# QCopterRC_LCD_Sch.net
KiCad netlist of a schematic drawn in Altium Designer
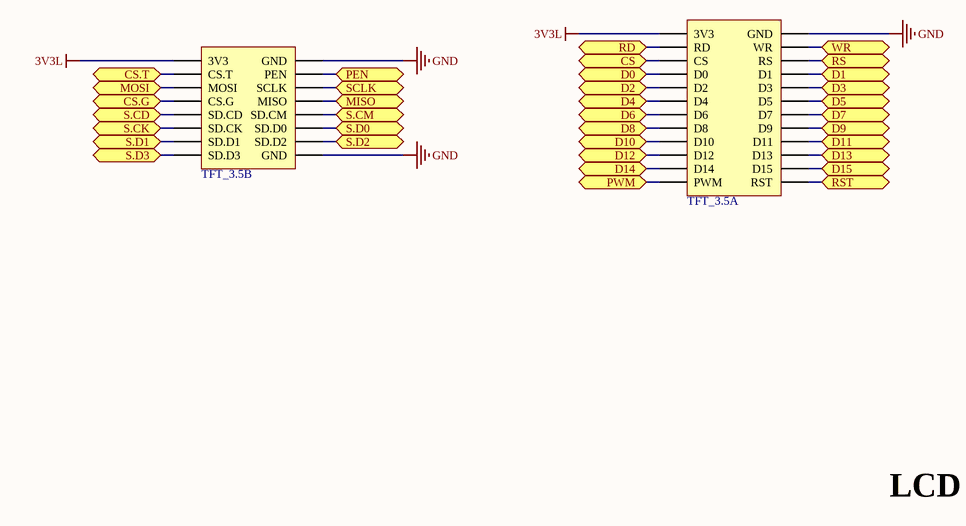
[diagram p0: QCopterRC_LCD_Sch.SchDoc]

(export (version "E")
  (design (tool "Eeschema 10.0.6"))
  (components
    (comp (ref "TFT_3.5")
      (value "TFT_3.5_480*320")
      (footprint "PCB_Module:TFT_3.5_480*320")
      (description "Module")
      (libsource (lib "SCH_Module") (part "TFT_3.5_480*320"))
    )
  )
  (nets
    (net (code "1") (name "/CS") (class "Default")
      (node (ref "TFT_3.5") (pin "5") (pinfunction "CS_5") (pintype "passive"))
    )
    (net (code "2") (name "/CS.G") (class "Default")
      (node (ref "TFT_3.5") (pin "31") (pinfunction "CS.G_31") (pintype "passive"))
    )
    (net (code "3") (name "/CS.T") (class "Default")
      (node (ref "TFT_3.5") (pin "27") (pinfunction "CS.T_27") (pintype "passive"))
    )
    (net (code "4") (name "/D0") (class "Default")
      (node (ref "TFT_3.5") (pin "7") (pinfunction "D0_7") (pintype "passive"))
    )
    (net (code "5") (name "/D1") (class "Default")
      (node (ref "TFT_3.5") (pin "8") (pinfunction "D1_8") (pintype "passive"))
    )
    (net (code "6") (name "/D2") (class "Default")
      (node (ref "TFT_3.5") (pin "9") (pinfunction "D2_9") (pintype "passive"))
    )
    (net (code "7") (name "/D3") (class "Default")
      (node (ref "TFT_3.5") (pin "10") (pinfunction "D3_10") (pintype "passive"))
    )
    (net (code "8") (name "/D4") (class "Default")
      (node (ref "TFT_3.5") (pin "11") (pinfunction "D4_11") (pintype "passive"))
    )
    (net (code "9") (name "/D5") (class "Default")
      (node (ref "TFT_3.5") (pin "12") (pinfunction "D5_12") (pintype "passive"))
    )
    (net (code "10") (name "/D6") (class "Default")
      (node (ref "TFT_3.5") (pin "13") (pinfunction "D6_13") (pintype "passive"))
    )
    (net (code "11") (name "/D7") (class "Default")
      (node (ref "TFT_3.5") (pin "14") (pinfunction "D7_14") (pintype "passive"))
    )
    (net (code "12") (name "/D8") (class "Default")
      (node (ref "TFT_3.5") (pin "15") (pinfunction "D8_15") (pintype "passive"))
    )
    (net (code "13") (name "/D9") (class "Default")
      (node (ref "TFT_3.5") (pin "16") (pinfunction "D9_16") (pintype "passive"))
    )
    (net (code "14") (name "/D10") (class "Default")
      (node (ref "TFT_3.5") (pin "17") (pinfunction "D10_17") (pintype "passive"))
    )
    (net (code "15") (name "/D11") (class "Default")
      (node (ref "TFT_3.5") (pin "18") (pinfunction "D11_18") (pintype "passive"))
    )
    (net (code "16") (name "/D12") (class "Default")
      (node (ref "TFT_3.5") (pin "19") (pinfunction "D12_19") (pintype "passive"))
    )
    (net (code "17") (name "/D13") (class "Default")
      (node (ref "TFT_3.5") (pin "20") (pinfunction "D13_20") (pintype "passive"))
    )
    (net (code "18") (name "/D14") (class "Default")
      (node (ref "TFT_3.5") (pin "21") (pinfunction "D14_21") (pintype "passive"))
    )
    (net (code "19") (name "/D15") (class "Default")
      (node (ref "TFT_3.5") (pin "22") (pinfunction "D15_22") (pintype "passive"))
    )
    (net (code "20") (name "/MISO") (class "Default")
      (node (ref "TFT_3.5") (pin "32") (pinfunction "MISO_32") (pintype "passive"))
    )
    (net (code "21") (name "/MOSI") (class "Default")
      (node (ref "TFT_3.5") (pin "29") (pinfunction "MOSI_29") (pintype "passive"))
    )
    (net (code "22") (name "/PEN") (class "Default")
      (node (ref "TFT_3.5") (pin "28") (pinfunction "PEN_28") (pintype "passive"))
    )
    (net (code "23") (name "/PWM") (class "Default")
      (node (ref "TFT_3.5") (pin "23") (pinfunction "PWM_23") (pintype "passive"))
    )
    (net (code "24") (name "/RD") (class "Default")
      (node (ref "TFT_3.5") (pin "3") (pinfunction "RD_3") (pintype "passive"))
    )
    (net (code "25") (name "/RS") (class "Default")
      (node (ref "TFT_3.5") (pin "6") (pinfunction "RS_6") (pintype "passive"))
    )
    (net (code "26") (name "/RST") (class "Default")
      (node (ref "TFT_3.5") (pin "24") (pinfunction "RST_24") (pintype "passive"))
    )
    (net (code "27") (name "/S.CD") (class "Default")
      (node (ref "TFT_3.5") (pin "33") (pinfunction "SD.CD_33") (pintype "passive"))
    )
    (net (code "28") (name "/S.CK") (class "Default")
      (node (ref "TFT_3.5") (pin "35") (pinfunction "SD.CK_35") (pintype "passive"))
    )
    (net (code "29") (name "/S.CM") (class "Default")
      (node (ref "TFT_3.5") (pin "34") (pinfunction "SD.CM_34") (pintype "passive"))
    )
    (net (code "30") (name "/S.D0") (class "Default")
      (node (ref "TFT_3.5") (pin "36") (pinfunction "SD.D0_36") (pintype "passive"))
    )
    (net (code "31") (name "/S.D1") (class "Default")
      (node (ref "TFT_3.5") (pin "37") (pinfunction "SD.D1_37") (pintype "passive"))
    )
    (net (code "32") (name "/S.D2") (class "Default")
      (node (ref "TFT_3.5") (pin "38") (pinfunction "SD.D2_38") (pintype "passive"))
    )
    (net (code "33") (name "/S.D3") (class "Default")
      (node (ref "TFT_3.5") (pin "39") (pinfunction "SD.D3_39") (pintype "passive"))
    )
    (net (code "34") (name "/SCLK") (class "Default")
      (node (ref "TFT_3.5") (pin "30") (pinfunction "SCLK_30") (pintype "passive"))
    )
    (net (code "35") (name "/WR") (class "Default")
      (node (ref "TFT_3.5") (pin "4") (pinfunction "WR_4") (pintype "passive"))
    )
    (net (code "36") (name "3V3L") (class "Default")
      (node (ref "TFT_3.5") (pin "1") (pinfunction "3V3_1") (pintype "passive"))
      (node (ref "TFT_3.5") (pin "25") (pinfunction "3V3_25") (pintype "passive"))
    )
    (net (code "37") (name "GND") (class "Default")
      (node (ref "TFT_3.5") (pin "2") (pinfunction "GND_2") (pintype "passive"))
      (node (ref "TFT_3.5") (pin "26") (pinfunction "GND_26") (pintype "passive"))
      (node (ref "TFT_3.5") (pin "40") (pinfunction "GND_40") (pintype "passive"))
    )
  )
)
